# Sheet.net
KiCad netlist of a schematic drawn in Altium Designer
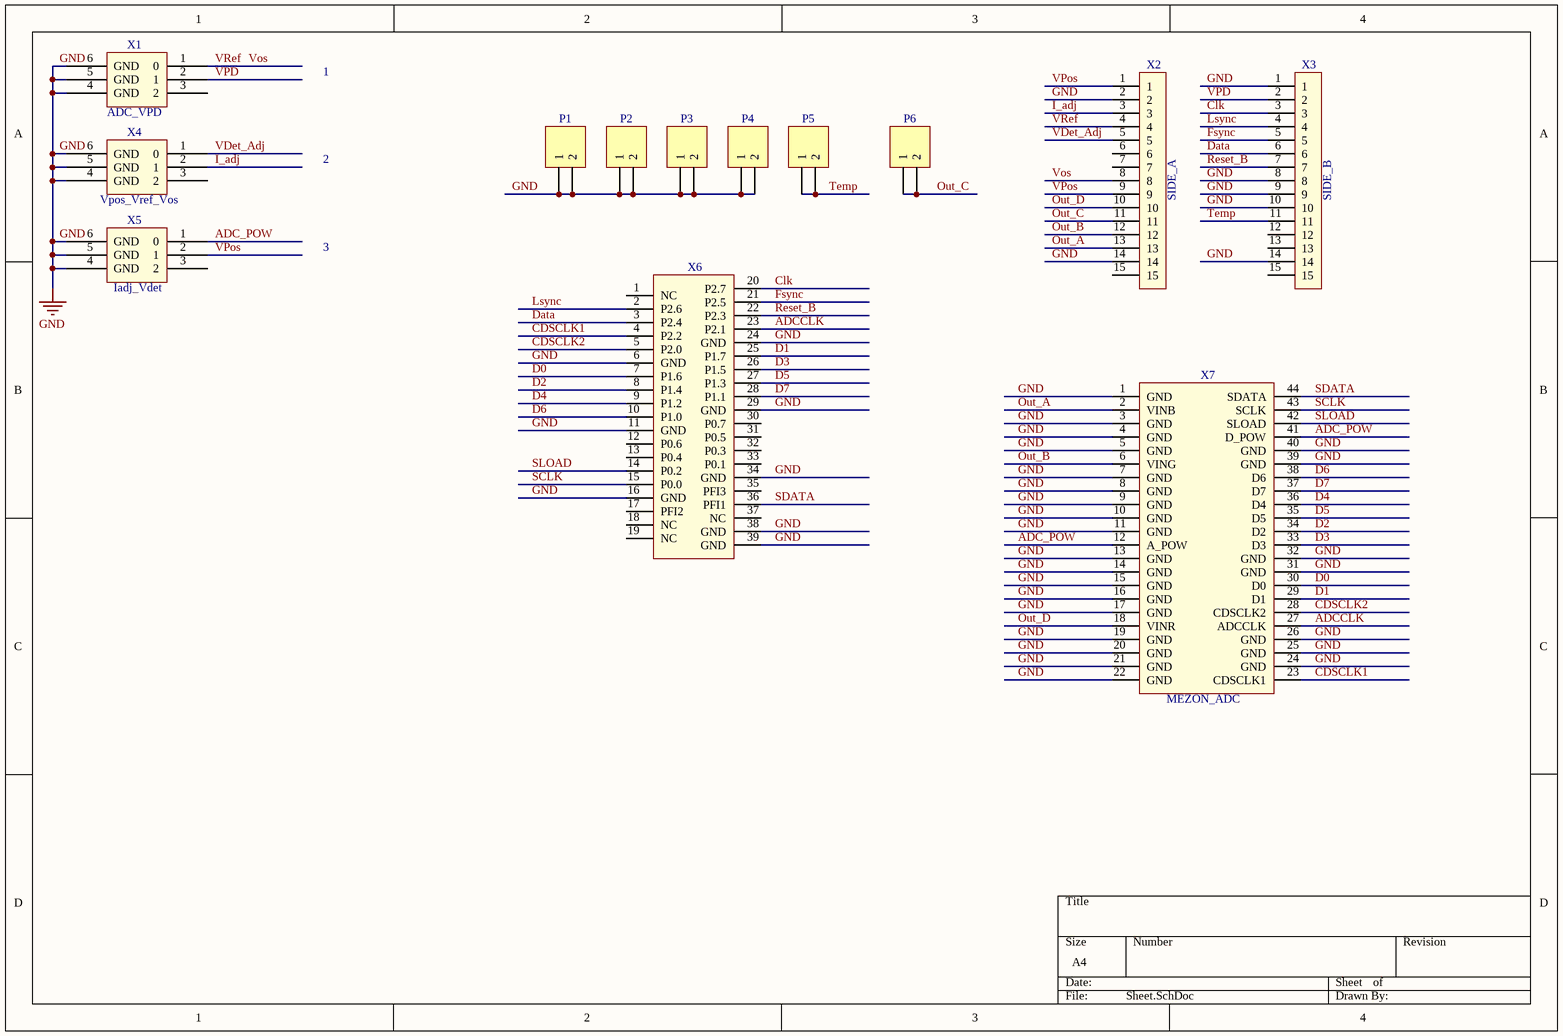
[diagram p0: Sheet.SchDoc]

(export (version "E")
  (design (tool "Eeschema 10.0.6"))
  (components
    (comp (ref "P1")
      (value "Header 2")
      (footprint "HDR1X2")
      (description "Header, 2-Pin")
      (fields (field (name "PUBLISHER") "Altium Limited"))
      (libsource (lib "Miscellaneous Connectors") (part "Header 2"))
    )
    (comp (ref "P2")
      (value "Header 2")
      (footprint "HDR1X2")
      (description "Header, 2-Pin")
      (fields (field (name "PUBLISHER") "Altium Limited"))
      (libsource (lib "Miscellaneous Connectors") (part "Header 2"))
    )
    (comp (ref "P3")
      (value "Header 2")
      (footprint "HDR1X2")
      (description "Header, 2-Pin")
      (fields (field (name "PUBLISHER") "Altium Limited"))
      (libsource (lib "Miscellaneous Connectors") (part "Header 2"))
    )
    (comp (ref "P4")
      (value "Header 2")
      (footprint "HDR1X2")
      (description "Header, 2-Pin")
      (fields (field (name "PUBLISHER") "Altium Limited"))
      (libsource (lib "Miscellaneous Connectors") (part "Header 2"))
    )
    (comp (ref "P5")
      (value "Header 2")
      (footprint "HDR1X2")
      (description "Header, 2-Pin")
      (fields (field (name "PUBLISHER") "Altium Limited"))
      (libsource (lib "Miscellaneous Connectors") (part "Header 2"))
    )
    (comp (ref "P6")
      (value "Header 2")
      (footprint "HDR1X2")
      (description "Header, 2-Pin")
      (fields (field (name "PUBLISHER") "Altium Limited"))
      (libsource (lib "Miscellaneous Connectors") (part "Header 2"))
    )
    (comp (ref "X1") (value "ADC_VPD") (footprint "POWER") (libsource (lib "Schlib") (part "POWER")))
    (comp (ref "X2")
      (value "SIDE_A")
      (footprint "INCAM_CONNECTOR_FPGA_15_QUADRO")
      (libsource (lib "Schlib") (part "INCAM_15_QUADRO"))
    )
    (comp (ref "X3")
      (value "SIDE_B")
      (footprint "INCAM_CONNECTOR_FPGA_15_QUADRO")
      (libsource (lib "Schlib") (part "INCAM_15_QUADRO"))
    )
    (comp (ref "X4") (value "Vpos_Vref_Vos") (footprint "POWER") (libsource (lib "Schlib") (part "POWER")))
    (comp (ref "X5") (value "Iadj_Vdet") (footprint "POWER") (libsource (lib "Schlib") (part "POWER")))
    (comp (ref "X6")
      (value "CHEAP_CON_37_FEMALE")
      (footprint "CHEAP_CONN_FEMALE")
      (libsource (lib "Schlib") (part "CHEAP_CON_37_FEMALE"))
    )
    (comp (ref "X7")
      (value "MEZON_ADC")
      (footprint "MEZON_ADC")
      (libsource (lib "Schlib") (part "MEZON_ADC"))
    )
  )
  (nets
    (net (code "1") (name "/ADCCLK") (class "Default")
      (node (ref "X6") (pin "23") (pinfunction "P2.1_23") (pintype "passive"))
      (node (ref "X7") (pin "27") (pinfunction "ADCCLK_27") (pintype "passive"))
    )
    (net (code "2") (name "/ADC_POW") (class "Default")
      (node (ref "X5") (pin "1") (pinfunction "0_1") (pintype "passive"))
      (node (ref "X7") (pin "12") (pinfunction "A_POW_12") (pintype "passive"))
      (node (ref "X7") (pin "41") (pinfunction "D_POW_41") (pintype "passive"))
    )
    (net (code "3") (name "/CDSCLK1") (class "Default")
      (node (ref "X6") (pin "4") (pinfunction "P2.2_4") (pintype "passive"))
      (node (ref "X7") (pin "23") (pinfunction "CDSCLK1_23") (pintype "passive"))
    )
    (net (code "4") (name "/CDSCLK2") (class "Default")
      (node (ref "X6") (pin "5") (pinfunction "P2.0_5") (pintype "passive"))
      (node (ref "X7") (pin "28") (pinfunction "CDSCLK2_28") (pintype "passive"))
    )
    (net (code "5") (name "/Clk") (class "Default")
      (node (ref "X3") (pin "3") (pinfunction "3_3") (pintype "passive"))
      (node (ref "X6") (pin "20") (pinfunction "P2.7_20") (pintype "passive"))
    )
    (net (code "6") (name "/D0") (class "Default")
      (node (ref "X6") (pin "7") (pinfunction "P1.6_7") (pintype "passive"))
      (node (ref "X7") (pin "30") (pinfunction "D0_30") (pintype "passive"))
    )
    (net (code "7") (name "/D1") (class "Default")
      (node (ref "X6") (pin "25") (pinfunction "P1.7_25") (pintype "passive"))
      (node (ref "X7") (pin "29") (pinfunction "D1_29") (pintype "passive"))
    )
    (net (code "8") (name "/D2") (class "Default")
      (node (ref "X6") (pin "8") (pinfunction "P1.4_8") (pintype "passive"))
      (node (ref "X7") (pin "34") (pinfunction "D2_34") (pintype "passive"))
    )
    (net (code "9") (name "/D3") (class "Default")
      (node (ref "X6") (pin "26") (pinfunction "P1.5_26") (pintype "passive"))
      (node (ref "X7") (pin "33") (pinfunction "D3_33") (pintype "passive"))
    )
    (net (code "10") (name "/D4") (class "Default")
      (node (ref "X6") (pin "9") (pinfunction "P1.2_9") (pintype "passive"))
      (node (ref "X7") (pin "36") (pinfunction "D4_36") (pintype "passive"))
    )
    (net (code "11") (name "/D5") (class "Default")
      (node (ref "X6") (pin "27") (pinfunction "P1.3_27") (pintype "passive"))
      (node (ref "X7") (pin "35") (pinfunction "D5_35") (pintype "passive"))
    )
    (net (code "12") (name "/D6") (class "Default")
      (node (ref "X6") (pin "10") (pinfunction "P1.0_10") (pintype "passive"))
      (node (ref "X7") (pin "38") (pinfunction "D6_38") (pintype "passive"))
    )
    (net (code "13") (name "/D7") (class "Default")
      (node (ref "X6") (pin "28") (pinfunction "P1.1_28") (pintype "passive"))
      (node (ref "X7") (pin "37") (pinfunction "D7_37") (pintype "passive"))
    )
    (net (code "14") (name "/Data") (class "Default")
      (node (ref "X3") (pin "6") (pinfunction "6_6") (pintype "passive"))
      (node (ref "X6") (pin "3") (pinfunction "P2.4_3") (pintype "passive"))
    )
    (net (code "15") (name "/Fsync") (class "Default")
      (node (ref "X3") (pin "5") (pinfunction "5_5") (pintype "passive"))
      (node (ref "X6") (pin "21") (pinfunction "P2.5_21") (pintype "passive"))
    )
    (net (code "16") (name "/I_adj") (class "Default")
      (node (ref "X2") (pin "3") (pinfunction "3_3") (pintype "passive"))
      (node (ref "X4") (pin "2") (pinfunction "1_2") (pintype "passive"))
    )
    (net (code "17") (name "/Lsync") (class "Default")
      (node (ref "X3") (pin "4") (pinfunction "4_4") (pintype "passive"))
      (node (ref "X6") (pin "2") (pinfunction "P2.6_2") (pintype "passive"))
    )
    (net (code "18") (name "/Out_A") (class "Default")
      (node (ref "X2") (pin "13") (pinfunction "13_13") (pintype "passive"))
      (node (ref "X7") (pin "2") (pinfunction "VINB_2") (pintype "passive"))
    )
    (net (code "19") (name "/Out_B") (class "Default")
      (node (ref "X2") (pin "12") (pinfunction "12_12") (pintype "passive"))
      (node (ref "X7") (pin "6") (pinfunction "VING_6") (pintype "passive"))
    )
    (net (code "20") (name "/Out_C") (class "Default")
      (node (ref "P6") (pin "1") (pinfunction "1_1") (pintype "passive"))
      (node (ref "P6") (pin "2") (pinfunction "2_2") (pintype "passive"))
      (node (ref "X2") (pin "11") (pinfunction "11_11") (pintype "passive"))
    )
    (net (code "21") (name "/Out_D") (class "Default")
      (node (ref "X2") (pin "10") (pinfunction "10_10") (pintype "passive"))
      (node (ref "X7") (pin "18") (pinfunction "VINR_18") (pintype "passive"))
    )
    (net (code "22") (name "/Reset_B") (class "Default")
      (node (ref "X3") (pin "7") (pinfunction "7_7") (pintype "passive"))
      (node (ref "X6") (pin "22") (pinfunction "P2.3_22") (pintype "passive"))
    )
    (net (code "23") (name "/SCLK") (class "Default")
      (node (ref "X6") (pin "15") (pinfunction "P0.0_15") (pintype "passive"))
      (node (ref "X7") (pin "43") (pinfunction "SCLK_43") (pintype "passive"))
    )
    (net (code "24") (name "/SDATA") (class "Default")
      (node (ref "X6") (pin "36") (pinfunction "PFI1_36") (pintype "passive"))
      (node (ref "X7") (pin "44") (pinfunction "SDATA_44") (pintype "passive"))
    )
    (net (code "25") (name "/SLOAD") (class "Default")
      (node (ref "X6") (pin "14") (pinfunction "P0.2_14") (pintype "passive"))
      (node (ref "X7") (pin "42") (pinfunction "SLOAD_42") (pintype "passive"))
    )
    (net (code "26") (name "/Temp") (class "Default")
      (node (ref "P5") (pin "1") (pinfunction "1_1") (pintype "passive"))
      (node (ref "P5") (pin "2") (pinfunction "2_2") (pintype "passive"))
      (node (ref "X3") (pin "11") (pinfunction "11_11") (pintype "passive"))
    )
    (net (code "27") (name "/VDet_Adj") (class "Default")
      (node (ref "X2") (pin "5") (pinfunction "5_5") (pintype "passive"))
      (node (ref "X4") (pin "1") (pinfunction "0_1") (pintype "passive"))
    )
    (net (code "28") (name "/VPD") (class "Default")
      (node (ref "X1") (pin "2") (pinfunction "1_2") (pintype "passive"))
      (node (ref "X3") (pin "2") (pinfunction "2_2") (pintype "passive"))
    )
    (net (code "29") (name "/VPos") (class "Default")
      (node (ref "X2") (pin "1") (pinfunction "1_1") (pintype "passive"))
      (node (ref "X2") (pin "9") (pinfunction "9_9") (pintype "passive"))
      (node (ref "X5") (pin "2") (pinfunction "1_2") (pintype "passive"))
    )
    (net (code "30") (name "/VRef") (class "Default")
      (node (ref "X1") (pin "1") (pinfunction "0_1") (pintype "passive"))
      (node (ref "X2") (pin "4") (pinfunction "4_4") (pintype "passive"))
      (node (ref "X2") (pin "8") (pinfunction "8_8") (pintype "passive"))
    )
    (net (code "31") (name "GND") (class "Default")
      (node (ref "P1") (pin "1") (pinfunction "1_1") (pintype "passive"))
      (node (ref "P1") (pin "2") (pinfunction "2_2") (pintype "passive"))
      (node (ref "P2") (pin "1") (pinfunction "1_1") (pintype "passive"))
      (node (ref "P2") (pin "2") (pinfunction "2_2") (pintype "passive"))
      (node (ref "P3") (pin "1") (pinfunction "1_1") (pintype "passive"))
      (node (ref "P3") (pin "2") (pinfunction "2_2") (pintype "passive"))
      (node (ref "P4") (pin "1") (pinfunction "1_1") (pintype "passive"))
      (node (ref "P4") (pin "2") (pinfunction "2_2") (pintype "passive"))
      (node (ref "X1") (pin "4") (pinfunction "GND_4") (pintype "passive"))
      (node (ref "X1") (pin "5") (pinfunction "GND_5") (pintype "passive"))
      (node (ref "X1") (pin "6") (pinfunction "GND_6") (pintype "passive"))
      (node (ref "X2") (pin "14") (pinfunction "14_14") (pintype "passive"))
      (node (ref "X2") (pin "2") (pinfunction "2_2") (pintype "passive"))
      (node (ref "X3") (pin "1") (pinfunction "1_1") (pintype "passive"))
      (node (ref "X3") (pin "10") (pinfunction "10_10") (pintype "passive"))
      (node (ref "X3") (pin "14") (pinfunction "14_14") (pintype "passive"))
      (node (ref "X3") (pin "8") (pinfunction "8_8") (pintype "passive"))
      (node (ref "X3") (pin "9") (pinfunction "9_9") (pintype "passive"))
      (node (ref "X4") (pin "4") (pinfunction "GND_4") (pintype "passive"))
      (node (ref "X4") (pin "5") (pinfunction "GND_5") (pintype "passive"))
      (node (ref "X4") (pin "6") (pinfunction "GND_6") (pintype "passive"))
      (node (ref "X5") (pin "4") (pinfunction "GND_4") (pintype "passive"))
      (node (ref "X5") (pin "5") (pinfunction "GND_5") (pintype "passive"))
      (node (ref "X5") (pin "6") (pinfunction "GND_6") (pintype "passive"))
      (node (ref "X6") (pin "11") (pinfunction "GND_11") (pintype "passive"))
      (node (ref "X6") (pin "16") (pinfunction "GND_16") (pintype "passive"))
      (node (ref "X6") (pin "24") (pinfunction "GND_24") (pintype "passive"))
      (node (ref "X6") (pin "29") (pinfunction "GND_29") (pintype "passive"))
      (node (ref "X6") (pin "34") (pinfunction "GND_34") (pintype "passive"))
      (node (ref "X6") (pin "38") (pinfunction "GND_38") (pintype "passive"))
      (node (ref "X6") (pin "39") (pinfunction "GND_39") (pintype "passive"))
      (node (ref "X6") (pin "6") (pinfunction "GND_6") (pintype "passive"))
      (node (ref "X7") (pin "1") (pinfunction "GND_1") (pintype "passive"))
      (node (ref "X7") (pin "10") (pinfunction "GND_10") (pintype "passive"))
      (node (ref "X7") (pin "11") (pinfunction "GND_11") (pintype "passive"))
      (node (ref "X7") (pin "13") (pinfunction "GND_13") (pintype "passive"))
      (node (ref "X7") (pin "14") (pinfunction "GND_14") (pintype "passive"))
      (node (ref "X7") (pin "15") (pinfunction "GND_15") (pintype "passive"))
      (node (ref "X7") (pin "16") (pinfunction "GND_16") (pintype "passive"))
      (node (ref "X7") (pin "17") (pinfunction "GND_17") (pintype "passive"))
      (node (ref "X7") (pin "19") (pinfunction "GND_19") (pintype "passive"))
      (node (ref "X7") (pin "20") (pinfunction "GND_20") (pintype "passive"))
      (node (ref "X7") (pin "21") (pinfunction "GND_21") (pintype "passive"))
      (node (ref "X7") (pin "22") (pinfunction "GND_22") (pintype "passive"))
      (node (ref "X7") (pin "24") (pinfunction "GND_24") (pintype "passive"))
      (node (ref "X7") (pin "25") (pinfunction "GND_25") (pintype "passive"))
      (node (ref "X7") (pin "26") (pinfunction "GND_26") (pintype "passive"))
      (node (ref "X7") (pin "3") (pinfunction "GND_3") (pintype "passive"))
      (node (ref "X7") (pin "31") (pinfunction "GND_31") (pintype "passive"))
      (node (ref "X7") (pin "32") (pinfunction "GND_32") (pintype "passive"))
      (node (ref "X7") (pin "39") (pinfunction "GND_39") (pintype "passive"))
      (node (ref "X7") (pin "4") (pinfunction "GND_4") (pintype "passive"))
      (node (ref "X7") (pin "40") (pinfunction "GND_40") (pintype "passive"))
      (node (ref "X7") (pin "5") (pinfunction "GND_5") (pintype "passive"))
      (node (ref "X7") (pin "7") (pinfunction "GND_7") (pintype "passive"))
      (node (ref "X7") (pin "8") (pinfunction "GND_8") (pintype "passive"))
      (node (ref "X7") (pin "9") (pinfunction "GND_9") (pintype "passive"))
    )
    (net (code "32") (name "unconnected-(X1-2-Pad3)") (class "Default")
      (node (ref "X1") (pin "3") (pinfunction "2_3") (pintype "passive"))
    )
    (net (code "33") (name "unconnected-(X2-Pad6)") (class "Default")
      (node (ref "X2") (pin "6") (pinfunction "6_6") (pintype "passive"))
    )
    (net (code "34") (name "unconnected-(X2-Pad7)") (class "Default")
      (node (ref "X2") (pin "7") (pinfunction "7_7") (pintype "passive"))
    )
    (net (code "35") (name "unconnected-(X2-Pad15)") (class "Default")
      (node (ref "X2") (pin "15") (pinfunction "15_15") (pintype "passive"))
    )
    (net (code "36") (name "unconnected-(X3-Pad12)") (class "Default")
      (node (ref "X3") (pin "12") (pinfunction "12_12") (pintype "passive"))
    )
    (net (code "37") (name "unconnected-(X3-Pad13)") (class "Default")
      (node (ref "X3") (pin "13") (pinfunction "13_13") (pintype "passive"))
    )
    (net (code "38") (name "unconnected-(X3-Pad15)") (class "Default")
      (node (ref "X3") (pin "15") (pinfunction "15_15") (pintype "passive"))
    )
    (net (code "39") (name "unconnected-(X4-2-Pad3)") (class "Default")
      (node (ref "X4") (pin "3") (pinfunction "2_3") (pintype "passive"))
    )
    (net (code "40") (name "unconnected-(X5-2-Pad3)") (class "Default")
      (node (ref "X5") (pin "3") (pinfunction "2_3") (pintype "passive"))
    )
    (net (code "41") (name "unconnected-(X6-NC-Pad1)") (class "Default")
      (node (ref "X6") (pin "1") (pinfunction "NC_1") (pintype "passive"))
    )
    (net (code "42") (name "unconnected-(X6-NC-Pad18)") (class "Default")
      (node (ref "X6") (pin "18") (pinfunction "NC_18") (pintype "passive"))
    )
    (net (code "43") (name "unconnected-(X6-NC-Pad19)") (class "Default")
      (node (ref "X6") (pin "19") (pinfunction "NC_19") (pintype "passive"))
    )
    (net (code "44") (name "unconnected-(X6-NC-Pad37)") (class "Default")
      (node (ref "X6") (pin "37") (pinfunction "NC_37") (pintype "passive"))
    )
    (net (code "45") (name "unconnected-(X6-P0.1-Pad33)") (class "Default")
      (node (ref "X6") (pin "33") (pinfunction "P0.1_33") (pintype "passive"))
    )
    (net (code "46") (name "unconnected-(X6-P0.3-Pad32)") (class "Default")
      (node (ref "X6") (pin "32") (pinfunction "P0.3_32") (pintype "passive"))
    )
    (net (code "47") (name "unconnected-(X6-P0.4-Pad13)") (class "Default")
      (node (ref "X6") (pin "13") (pinfunction "P0.4_13") (pintype "passive"))
    )
    (net (code "48") (name "unconnected-(X6-P0.5-Pad31)") (class "Default")
      (node (ref "X6") (pin "31") (pinfunction "P0.5_31") (pintype "passive"))
    )
    (net (code "49") (name "unconnected-(X6-P0.6-Pad12)") (class "Default")
      (node (ref "X6") (pin "12") (pinfunction "P0.6_12") (pintype "passive"))
    )
    (net (code "50") (name "unconnected-(X6-P0.7-Pad30)") (class "Default")
      (node (ref "X6") (pin "30") (pinfunction "P0.7_30") (pintype "passive"))
    )
    (net (code "51") (name "unconnected-(X6-PFI2-Pad17)") (class "Default")
      (node (ref "X6") (pin "17") (pinfunction "PFI2_17") (pintype "passive"))
    )
    (net (code "52") (name "unconnected-(X6-PFI3-Pad35)") (class "Default")
      (node (ref "X6") (pin "35") (pinfunction "PFI3_35") (pintype "passive"))
    )
  )
)
